# SCH_Sensor_Frame_PCB_2022-08-15.net
KiCad netlist of a schematic drawn in EasyEDA
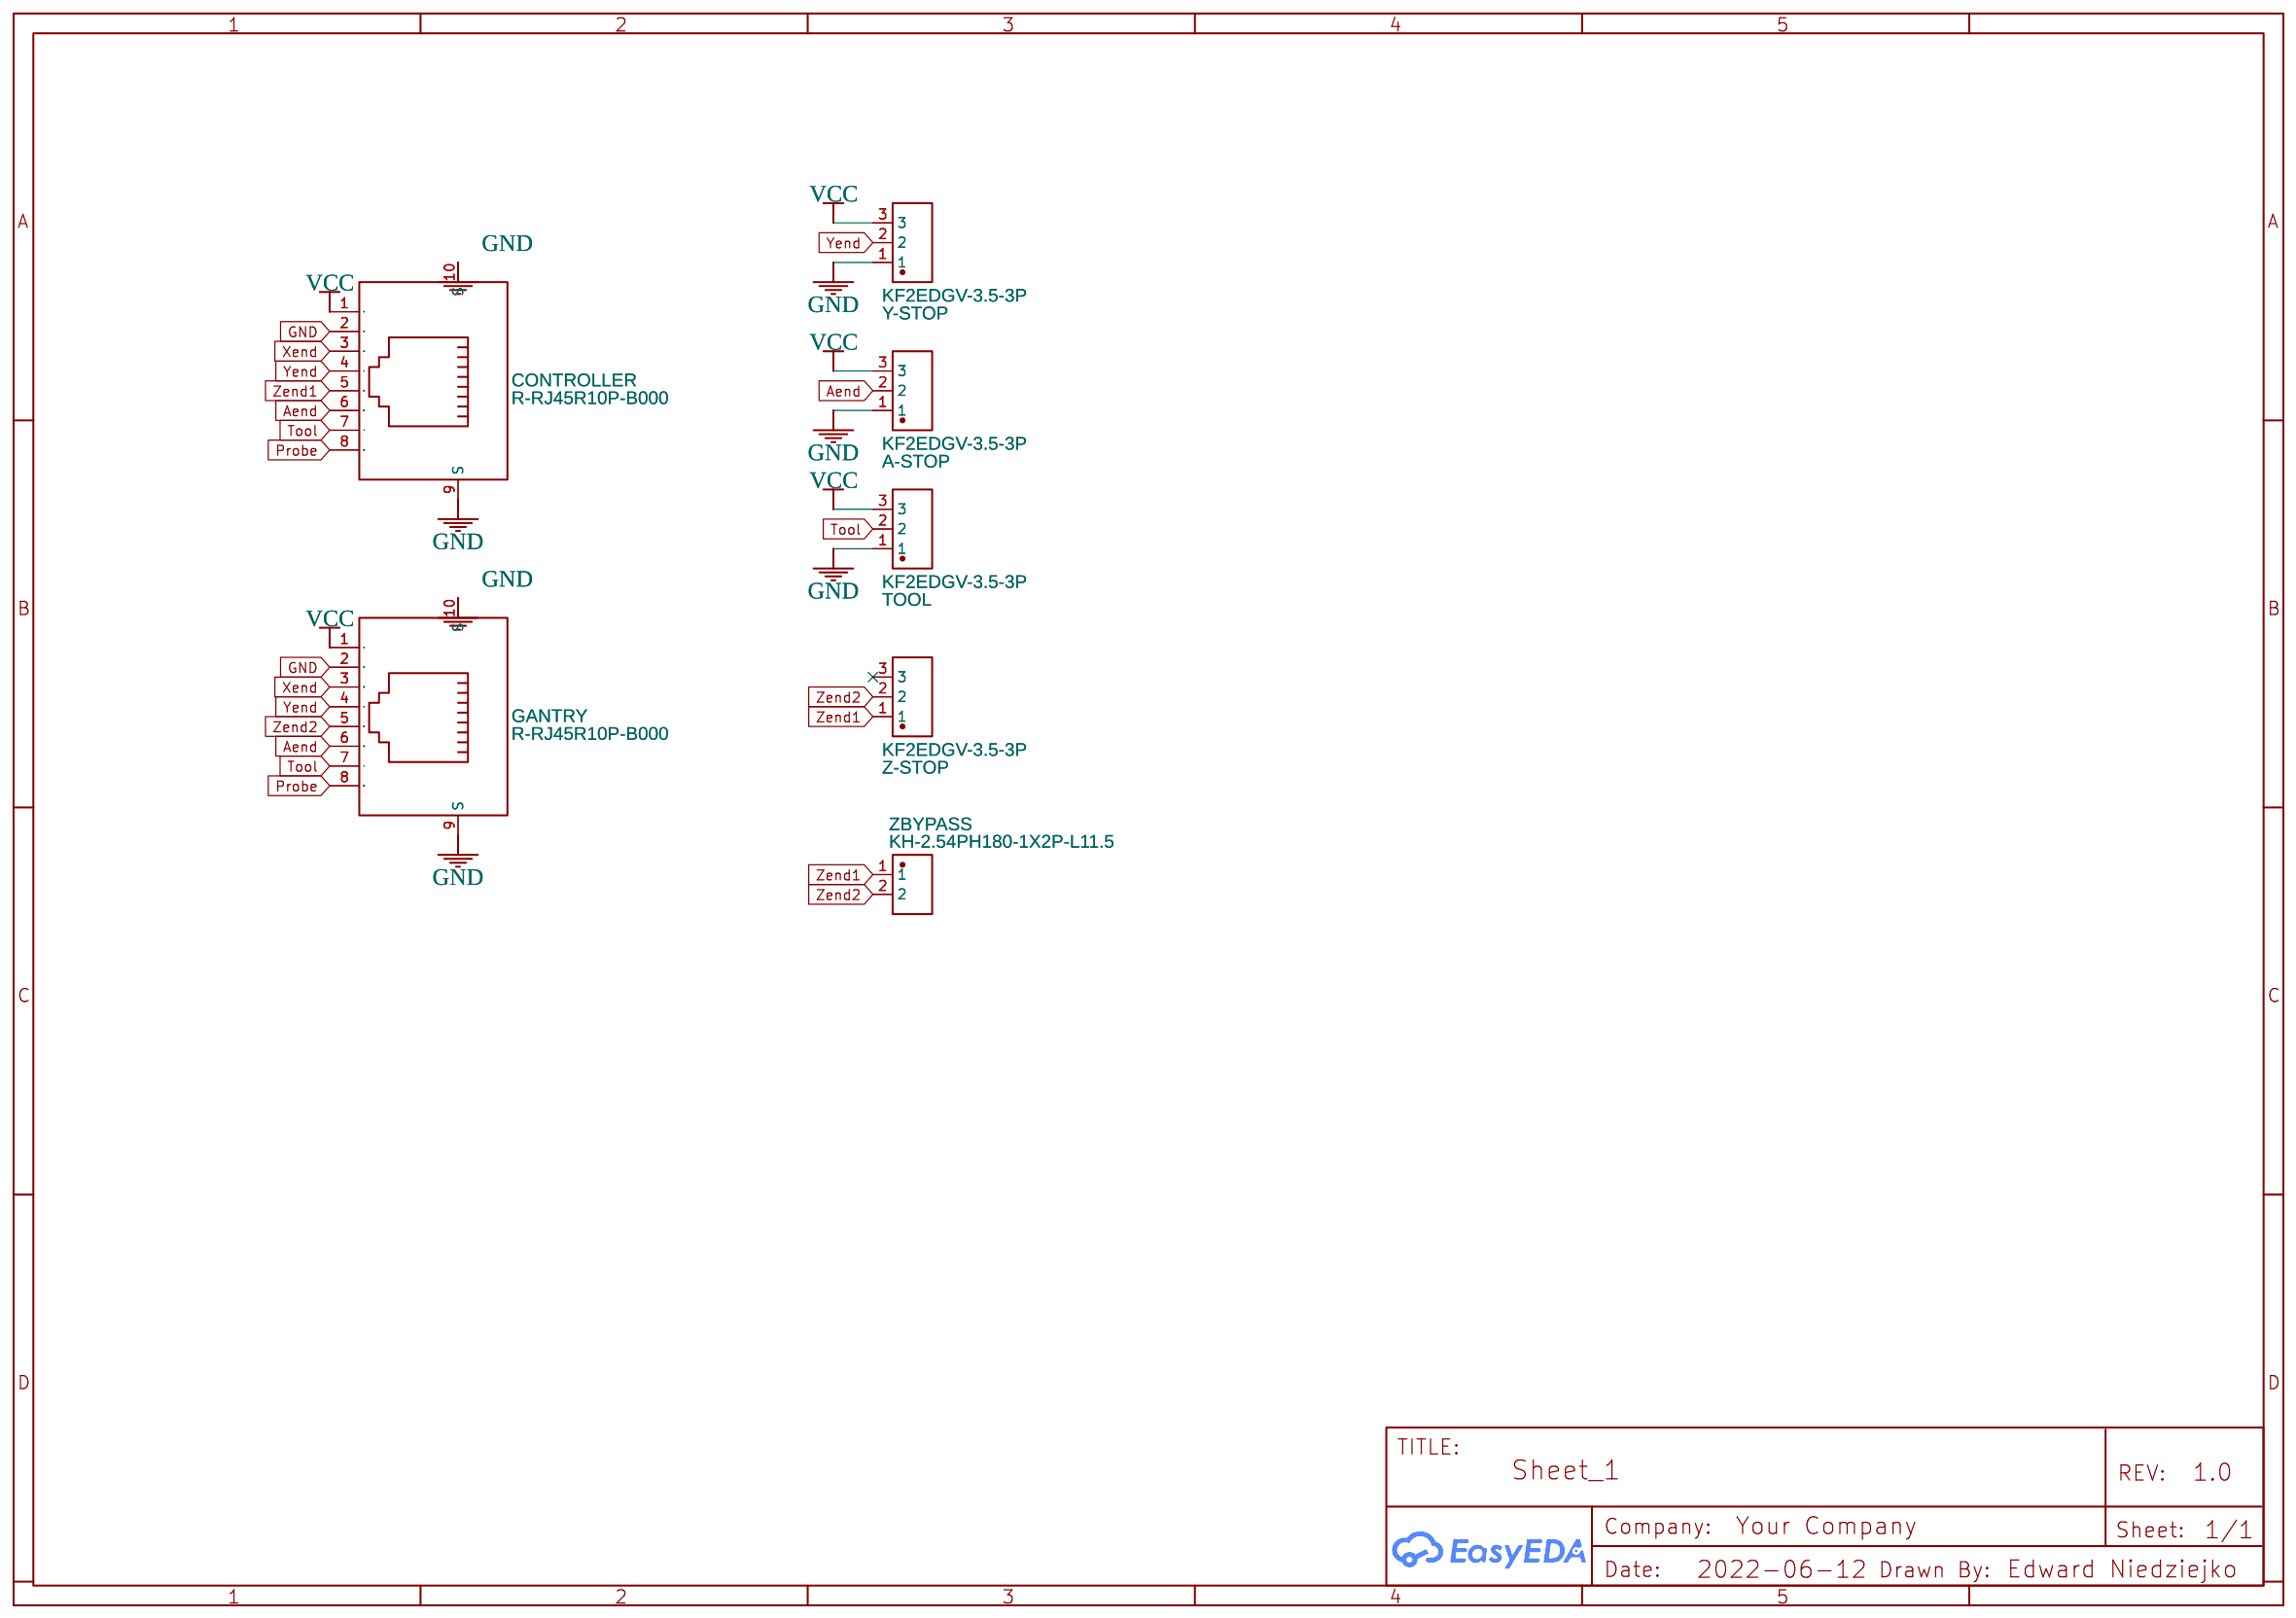
[diagram p0: schematic sheet]

(export (version "E")
  (design (tool "Eeschema 10.0.6"))
  (components
    (comp (ref "A-STOP")
      (value "KF2EDGV-3.5-3P")
      (fields (field (name "BOM_Supplier Part") "C441322"))
      (libsource (lib "") (part "KF2EDGV-3.5-3P_2"))
    )
    (comp (ref "CONTROLLER")
      (value "R-RJ45R10P-B000")
      (fields (field (name "BOM_Supplier Part") "C386758"))
      (libsource (lib "") (part "R-RJ45R10P-B000_1"))
    )
    (comp (ref "GANTRY")
      (value "R-RJ45R10P-B000")
      (fields (field (name "BOM_Supplier Part") "C386758"))
      (libsource (lib "") (part "R-RJ45R10P-B000"))
    )
    (comp (ref "TOOL")
      (value "KF2EDGV-3.5-3P")
      (fields (field (name "BOM_Supplier Part") "C441322"))
      (libsource (lib "") (part "KF2EDGV-3.5-3P"))
    )
    (comp (ref "Y-STOP")
      (value "KF2EDGV-3.5-3P")
      (fields (field (name "BOM_Supplier Part") "C441322"))
      (libsource (lib "") (part "KF2EDGV-3.5-3P_3"))
    )
    (comp (ref "Z-STOP")
      (value "KF2EDGV-3.5-3P")
      (fields (field (name "BOM_Supplier Part") "C441322"))
      (libsource (lib "") (part "KF2EDGV-3.5-3P_1"))
    )
    (comp (ref "ZBYPASS")
      (value "KH-2.54PH180-1X2P-L11.5")
      (fields (field (name "BOM_Supplier Part") "C2905434"))
      (libsource (lib "") (part "KH-2.54PH180-1X2P-L11.5"))
    )
  )
  (nets
    (net (code "1") (name "Aend") (class "Default")
      (node (ref "A-STOP") (pin "2") (pinfunction "2_2") (pintype "unspecified"))
      (node (ref "CONTROLLER") (pin "6") (pinfunction "6_6") (pintype "unspecified"))
      (node (ref "GANTRY") (pin "6") (pinfunction "6_6") (pintype "unspecified"))
    )
    (net (code "2") (name "GND") (class "Default")
      (node (ref "A-STOP") (pin "1") (pinfunction "1_1") (pintype "unspecified"))
      (node (ref "CONTROLLER") (pin "10") (pinfunction "S_10") (pintype "unspecified"))
      (node (ref "CONTROLLER") (pin "2") (pinfunction "2_2") (pintype "unspecified"))
      (node (ref "CONTROLLER") (pin "9") (pinfunction "S_9") (pintype "unspecified"))
      (node (ref "GANTRY") (pin "10") (pinfunction "S_10") (pintype "unspecified"))
      (node (ref "GANTRY") (pin "2") (pinfunction "2_2") (pintype "unspecified"))
      (node (ref "GANTRY") (pin "9") (pinfunction "S_9") (pintype "unspecified"))
      (node (ref "TOOL") (pin "1") (pinfunction "1_1") (pintype "unspecified"))
      (node (ref "Y-STOP") (pin "1") (pinfunction "1_1") (pintype "unspecified"))
    )
    (net (code "3") (name "Probe") (class "Default")
      (node (ref "CONTROLLER") (pin "8") (pinfunction "8_8") (pintype "unspecified"))
      (node (ref "GANTRY") (pin "8") (pinfunction "8_8") (pintype "unspecified"))
    )
    (net (code "4") (name "Tool") (class "Default")
      (node (ref "CONTROLLER") (pin "7") (pinfunction "7_7") (pintype "unspecified"))
      (node (ref "GANTRY") (pin "7") (pinfunction "7_7") (pintype "unspecified"))
      (node (ref "TOOL") (pin "2") (pinfunction "2_2") (pintype "unspecified"))
    )
    (net (code "5") (name "VCC") (class "Default")
      (node (ref "A-STOP") (pin "3") (pinfunction "3_3") (pintype "unspecified"))
      (node (ref "CONTROLLER") (pin "1") (pinfunction "1_1") (pintype "unspecified"))
      (node (ref "GANTRY") (pin "1") (pinfunction "1_1") (pintype "unspecified"))
      (node (ref "TOOL") (pin "3") (pinfunction "3_3") (pintype "unspecified"))
      (node (ref "Y-STOP") (pin "3") (pinfunction "3_3") (pintype "unspecified"))
    )
    (net (code "6") (name "Xend") (class "Default")
      (node (ref "CONTROLLER") (pin "3") (pinfunction "3_3") (pintype "unspecified"))
      (node (ref "GANTRY") (pin "3") (pinfunction "3_3") (pintype "unspecified"))
    )
    (net (code "7") (name "Yend") (class "Default")
      (node (ref "CONTROLLER") (pin "4") (pinfunction "4_4") (pintype "unspecified"))
      (node (ref "GANTRY") (pin "4") (pinfunction "4_4") (pintype "unspecified"))
      (node (ref "Y-STOP") (pin "2") (pinfunction "2_2") (pintype "unspecified"))
    )
    (net (code "8") (name "Zend1") (class "Default")
      (node (ref "CONTROLLER") (pin "5") (pinfunction "5_5") (pintype "unspecified"))
      (node (ref "Z-STOP") (pin "1") (pinfunction "1_1") (pintype "unspecified"))
      (node (ref "ZBYPASS") (pin "1") (pinfunction "1_1") (pintype "unspecified"))
    )
    (net (code "9") (name "Zend2") (class "Default")
      (node (ref "GANTRY") (pin "5") (pinfunction "5_5") (pintype "unspecified"))
      (node (ref "Z-STOP") (pin "2") (pinfunction "2_2") (pintype "unspecified"))
      (node (ref "ZBYPASS") (pin "2") (pinfunction "2_2") (pintype "unspecified"))
    )
    (net (code "10") (name "unconnected-(Z-STOP-Pad3)") (class "Default")
      (node (ref "Z-STOP") (pin "3") (pinfunction "3_3") (pintype "unspecified+no_connect"))
    )
  )
)
